# utility_hat.net
KiCad netlist of a schematic drawn in EAGLE
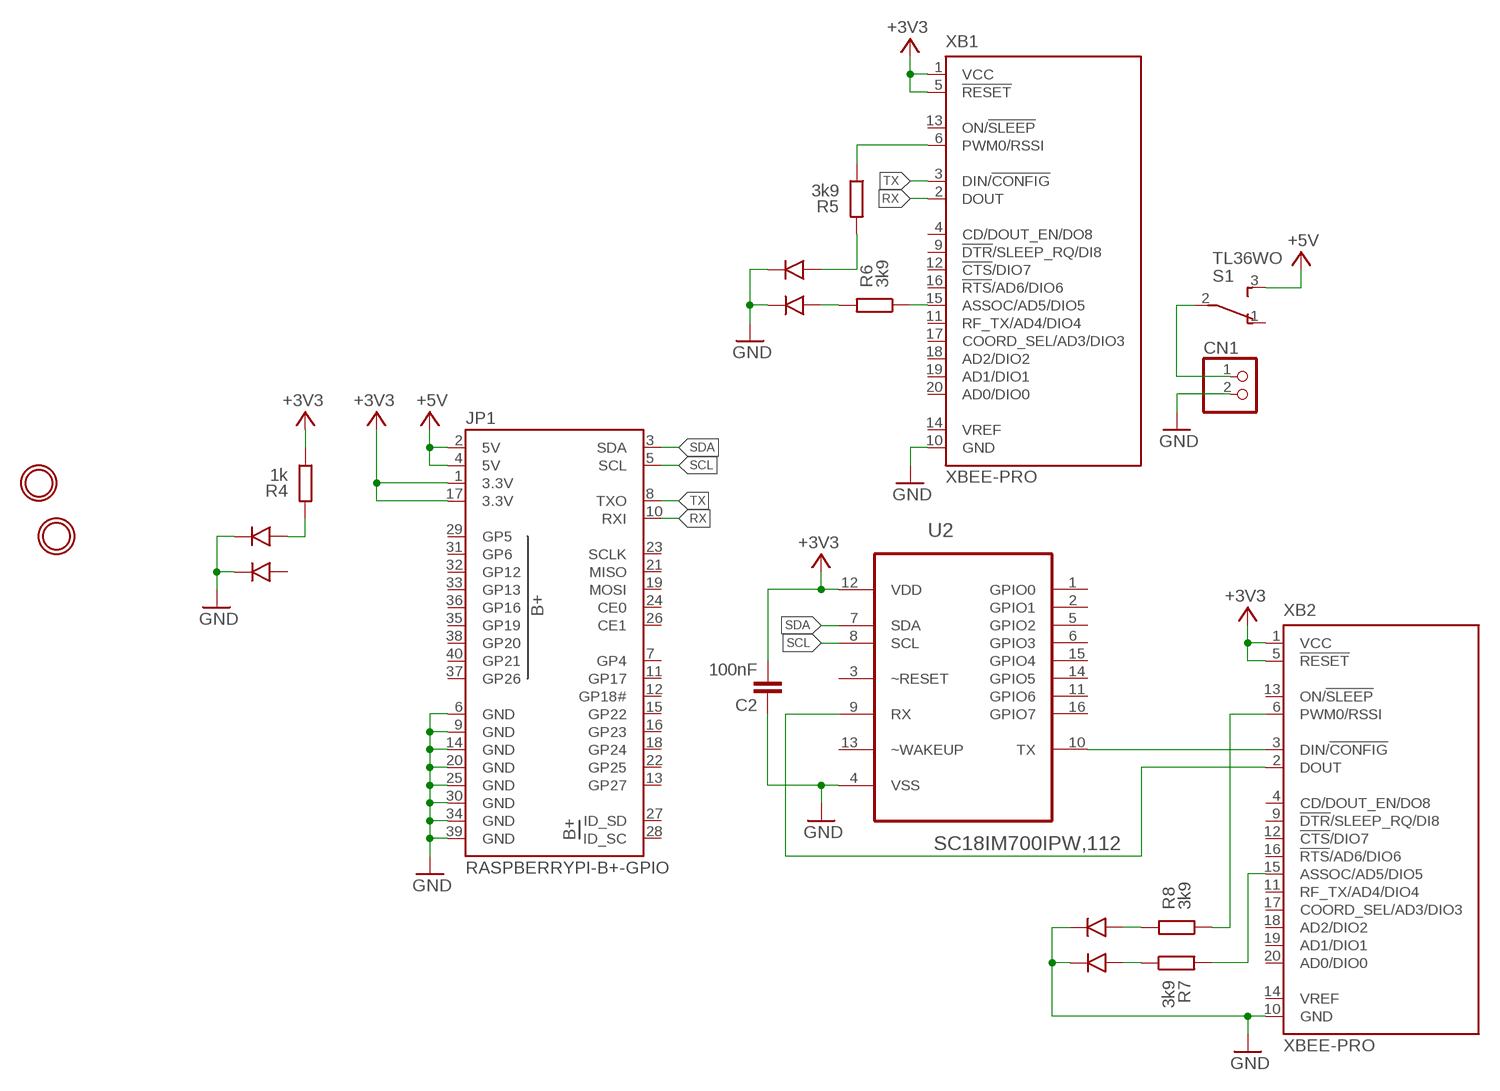
[diagram p0: schematic, sheet 1]

(export (version "E")
  (design (tool "Eeschema 10.0.6"))
  (components
    (comp (ref "C2")
      (value "100nF")
      (footprint "eagle-import:C0805K")
      (libsource (lib "eagle-import") (part "C-EUC0805K"))
    )
    (comp (ref "CN1")
      (value "JST_2PIN")
      (footprint "eagle-import:JSTPH2")
      (libsource (lib "eagle-import") (part "JST_2PIN"))
    )
    (comp (ref "JP1")
      (value "RASPBERRYPI-B+-GPIO")
      (footprint "eagle-import:2X20-SHROUDED")
      (libsource (lib "eagle-import") (part "RASPBERRYPI-B+-GPIO"))
    )
    (comp (ref "R4")
      (value "1k")
      (footprint "eagle-import:M0805")
      (fields (field (name "TOLERANCE") "5%"))
      (libsource (lib "eagle-import") (part "R-EU_M0805"))
    )
    (comp (ref "R5")
      (value "3k9")
      (footprint "eagle-import:M0805")
      (fields (field (name "TOLERANCE") "5%"))
      (libsource (lib "eagle-import") (part "R-EU_M0805"))
    )
    (comp (ref "R6")
      (value "3k9")
      (footprint "eagle-import:M0805")
      (fields (field (name "TOLERANCE") "5%"))
      (libsource (lib "eagle-import") (part "R-EU_M0805"))
    )
    (comp (ref "R7")
      (value "3k9")
      (footprint "eagle-import:M0805")
      (fields (field (name "TOLERANCE") "5%"))
      (libsource (lib "eagle-import") (part "R-EU_M0805"))
    )
    (comp (ref "R8")
      (value "3k9")
      (footprint "eagle-import:M0805")
      (fields (field (name "TOLERANCE") "5%"))
      (libsource (lib "eagle-import") (part "R-EU_M0805"))
    )
    (comp (ref "S1")
      (value "TL36WO")
      (footprint "eagle-import:TL3XWO")
      (libsource (lib "eagle-import") (part "TL36WO"))
    )
    (comp (ref "U$1")
      (value "BI-LEVEL-LED-INDICATOR")
      (footprint "eagle-import:BI-LEVEL-LED-INDICATOR")
      (libsource (lib "eagle-import") (part "BI-LEVEL-LED-INDICATOR"))
    )
    (comp (ref "U$2")
      (value "BI-LEVEL-LED-INDICATOR")
      (footprint "eagle-import:BI-LEVEL-LED-INDICATOR")
      (libsource (lib "eagle-import") (part "BI-LEVEL-LED-INDICATOR"))
    )
    (comp (ref "U$3")
      (value "BI-LEVEL-LED-INDICATOR")
      (footprint "eagle-import:BI-LEVEL-LED-INDICATOR")
      (libsource (lib "eagle-import") (part "BI-LEVEL-LED-INDICATOR"))
    )
    (comp (ref "U$4")
      (value "MOUNTINGHOLE3.0THIN")
      (footprint "eagle-import:MOUNTINGHOLE_3.0_PLATEDTHIN")
      (libsource (lib "eagle-import") (part "MOUNTINGHOLE3.0THIN"))
    )
    (comp (ref "U$5")
      (value "MOUNTINGHOLE3.0THIN")
      (footprint "eagle-import:MOUNTINGHOLE_3.0_PLATEDTHIN")
      (libsource (lib "eagle-import") (part "MOUNTINGHOLE3.0THIN"))
    )
    (comp (ref "U2")
      (value "SC18IM700IPW,112")
      (footprint "eagle-import:SOP65P640X110-16N")
      (libsource (lib "eagle-import") (part "SC18IM700IPW,112"))
    )
    (comp (ref "XB1")
      (value "XBEE-PRO")
      (footprint "eagle-import:XBEE-PRO")
      (fields (field (name "MPN") "XBP24-AWI-001"))
      (libsource (lib "eagle-import") (part "XBEE-PRO"))
    )
    (comp (ref "XB2")
      (value "XBEE-PRO")
      (footprint "eagle-import:XBEE-PRO")
      (fields
        (field (name "MPN") "XBP24-AWI-001")
        (field (name "MPN_1") "XBP24-AWI-001")
        (field (name "OC_FARNELL") "1337916")
        (field (name "OC_NEWARK") "42M2667")
      )
      (libsource (lib "eagle-import") (part "XBEE-PRO"))
    )
  )
  (nets
    (net (code "1") (name "+3V3") (class "Default")
      (node (ref "C2") (pin "2") (pinfunction "2_2") (pintype "passive"))
      (node (ref "JP1") (pin "1") (pinfunction "3.3V_1") (pintype "power_in"))
      (node (ref "JP1") (pin "17") (pinfunction "3.3V_17") (pintype "power_in"))
      (node (ref "R4") (pin "1") (pinfunction "1_1") (pintype "passive"))
      (node (ref "U2") (pin "12") (pinfunction "VDD_12") (pintype "power_in"))
      (node (ref "XB1") (pin "1") (pinfunction "VCC_1") (pintype "power_in"))
      (node (ref "XB1") (pin "5") (pinfunction "~{RESET}_5") (pintype "input"))
      (node (ref "XB2") (pin "1") (pinfunction "VCC_1") (pintype "power_in"))
      (node (ref "XB2") (pin "5") (pinfunction "~{RESET}_5") (pintype "input"))
    )
    (net (code "2") (name "+5V") (class "Default")
      (node (ref "JP1") (pin "2") (pinfunction "5V_2") (pintype "power_in"))
      (node (ref "JP1") (pin "4") (pinfunction "5V_4") (pintype "power_in"))
      (node (ref "S1") (pin "3") (pinfunction "S_3") (pintype "passive"))
    )
    (net (code "3") (name "GND") (class "Default")
      (node (ref "C2") (pin "1") (pinfunction "1_1") (pintype "passive"))
      (node (ref "CN1") (pin "2") (pinfunction "2_2") (pintype "passive"))
      (node (ref "JP1") (pin "14") (pinfunction "GND_14") (pintype "power_in"))
      (node (ref "JP1") (pin "20") (pinfunction "GND_20") (pintype "power_in"))
      (node (ref "JP1") (pin "25") (pinfunction "GND_25") (pintype "power_in"))
      (node (ref "JP1") (pin "30") (pinfunction "GND_30") (pintype "power_in"))
      (node (ref "JP1") (pin "34") (pinfunction "GND_34") (pintype "power_in"))
      (node (ref "JP1") (pin "39") (pinfunction "GND_39") (pintype "power_in"))
      (node (ref "JP1") (pin "6") (pinfunction "GND_6") (pintype "power_in"))
      (node (ref "JP1") (pin "9") (pinfunction "GND_9") (pintype "power_in"))
      (node (ref "U$1") (pin "CATHODE1") (pinfunction "CATHODE1_CATHODE1") (pintype "bidirectional"))
      (node (ref "U$1") (pin "CATHODE2") (pinfunction "CATHODE2_CATHODE2") (pintype "bidirectional"))
      (node (ref "U$2") (pin "CATHODE1") (pinfunction "CATHODE1_CATHODE1") (pintype "bidirectional"))
      (node (ref "U$2") (pin "CATHODE2") (pinfunction "CATHODE2_CATHODE2") (pintype "bidirectional"))
      (node (ref "U$3") (pin "CATHODE1") (pinfunction "CATHODE1_CATHODE1") (pintype "bidirectional"))
      (node (ref "U$3") (pin "CATHODE2") (pinfunction "CATHODE2_CATHODE2") (pintype "bidirectional"))
      (node (ref "U2") (pin "4") (pinfunction "VSS_4") (pintype "passive"))
      (node (ref "XB1") (pin "10") (pinfunction "GND_10") (pintype "power_in"))
      (node (ref "XB2") (pin "10") (pinfunction "GND_10") (pintype "power_in"))
    )
    (net (code "4") (name "Net-(R4-Pad2)") (class "Default")
      (node (ref "R4") (pin "2") (pinfunction "2_2") (pintype "passive"))
      (node (ref "U$3") (pin "ANODE1") (pinfunction "ANODE1_ANODE1") (pintype "bidirectional"))
    )
    (net (code "5") (name "Net-(R5-Pad2)") (class "Default")
      (node (ref "R5") (pin "2") (pinfunction "2_2") (pintype "passive"))
      (node (ref "U$1") (pin "ANODE1") (pinfunction "ANODE1_ANODE1") (pintype "bidirectional"))
    )
    (net (code "6") (name "Net-(R6-Pad2)") (class "Default")
      (node (ref "R6") (pin "2") (pinfunction "2_2") (pintype "passive"))
      (node (ref "U$1") (pin "ANODE2") (pinfunction "ANODE2_ANODE2") (pintype "bidirectional"))
    )
    (net (code "7") (name "Net-(R7-Pad1)") (class "Default")
      (node (ref "R7") (pin "1") (pinfunction "1_1") (pintype "passive"))
      (node (ref "U$2") (pin "ANODE2") (pinfunction "ANODE2_ANODE2") (pintype "bidirectional"))
    )
    (net (code "8") (name "Net-(R8-Pad2)") (class "Default")
      (node (ref "R8") (pin "2") (pinfunction "2_2") (pintype "passive"))
      (node (ref "U$2") (pin "ANODE1") (pinfunction "ANODE1_ANODE1") (pintype "bidirectional"))
    )
    (net (code "9") (name "Net-(S1-P)") (class "Default")
      (node (ref "CN1") (pin "1") (pinfunction "1_1") (pintype "passive"))
      (node (ref "S1") (pin "2") (pinfunction "P_2") (pintype "passive"))
    )
    (net (code "10") (name "Net-(U2-RX)") (class "Default")
      (node (ref "U2") (pin "9") (pinfunction "RX_9") (pintype "input"))
      (node (ref "XB2") (pin "2") (pinfunction "DOUT_2") (pintype "output"))
    )
    (net (code "11") (name "Net-(U2-TX)") (class "Default")
      (node (ref "U2") (pin "10") (pinfunction "TX_10") (pintype "output"))
      (node (ref "XB2") (pin "3") (pinfunction "DIN/~{CONFIG}_3") (pintype "input"))
    )
    (net (code "12") (name "Net-(XB1-ASSOC{slash}AD5{slash}DIO5)") (class "Default")
      (node (ref "R6") (pin "1") (pinfunction "1_1") (pintype "passive"))
      (node (ref "XB1") (pin "15") (pinfunction "ASSOC/AD5/DIO5_15") (pintype "bidirectional"))
    )
    (net (code "13") (name "Net-(XB1-PWM0{slash}RSSI)") (class "Default")
      (node (ref "R5") (pin "1") (pinfunction "1_1") (pintype "passive"))
      (node (ref "XB1") (pin "6") (pinfunction "PWM0/RSSI_6") (pintype "output"))
    )
    (net (code "14") (name "Net-(XB2-ASSOC{slash}AD5{slash}DIO5)") (class "Default")
      (node (ref "R7") (pin "2") (pinfunction "2_2") (pintype "passive"))
      (node (ref "XB2") (pin "15") (pinfunction "ASSOC/AD5/DIO5_15") (pintype "bidirectional"))
    )
    (net (code "15") (name "Net-(XB2-PWM0{slash}RSSI)") (class "Default")
      (node (ref "R8") (pin "1") (pinfunction "1_1") (pintype "passive"))
      (node (ref "XB2") (pin "6") (pinfunction "PWM0/RSSI_6") (pintype "output"))
    )
    (net (code "16") (name "RX") (class "Default")
      (node (ref "JP1") (pin "10") (pinfunction "RXI_10") (pintype "input"))
      (node (ref "XB1") (pin "2") (pinfunction "DOUT_2") (pintype "output"))
    )
    (net (code "17") (name "SCL") (class "Default")
      (node (ref "JP1") (pin "5") (pinfunction "SCL_5") (pintype "bidirectional"))
      (node (ref "U2") (pin "8") (pinfunction "SCL_8") (pintype "input"))
    )
    (net (code "18") (name "SDA") (class "Default")
      (node (ref "JP1") (pin "3") (pinfunction "SDA_3") (pintype "bidirectional"))
      (node (ref "U2") (pin "7") (pinfunction "SDA_7") (pintype "bidirectional"))
    )
    (net (code "19") (name "TX") (class "Default")
      (node (ref "JP1") (pin "8") (pinfunction "TXO_8") (pintype "output"))
      (node (ref "XB1") (pin "3") (pinfunction "DIN/~{CONFIG}_3") (pintype "input"))
    )
    (net (code "20") (name "unconnected-(JP1-CE0-Pad24)") (class "Default")
      (node (ref "JP1") (pin "24") (pinfunction "CE0_24") (pintype "output"))
    )
    (net (code "21") (name "unconnected-(JP1-CE1-Pad26)") (class "Default")
      (node (ref "JP1") (pin "26") (pinfunction "CE1_26") (pintype "output"))
    )
    (net (code "22") (name "unconnected-(JP1-GP4-Pad7)") (class "Default")
      (node (ref "JP1") (pin "7") (pinfunction "GP4_7") (pintype "bidirectional"))
    )
    (net (code "23") (name "unconnected-(JP1-GP5-Pad29)") (class "Default")
      (node (ref "JP1") (pin "29") (pinfunction "GP5_29") (pintype "bidirectional"))
    )
    (net (code "24") (name "unconnected-(JP1-GP6-Pad31)") (class "Default")
      (node (ref "JP1") (pin "31") (pinfunction "GP6_31") (pintype "bidirectional"))
    )
    (net (code "25") (name "unconnected-(JP1-GP12-Pad32)") (class "Default")
      (node (ref "JP1") (pin "32") (pinfunction "GP12_32") (pintype "bidirectional"))
    )
    (net (code "26") (name "unconnected-(JP1-GP13-Pad33)") (class "Default")
      (node (ref "JP1") (pin "33") (pinfunction "GP13_33") (pintype "bidirectional"))
    )
    (net (code "27") (name "unconnected-(JP1-GP16-Pad36)") (class "Default")
      (node (ref "JP1") (pin "36") (pinfunction "GP16_36") (pintype "bidirectional"))
    )
    (net (code "28") (name "unconnected-(JP1-GP17-Pad11)") (class "Default")
      (node (ref "JP1") (pin "11") (pinfunction "GP17_11") (pintype "bidirectional"))
    )
    (net (code "29") (name "unconnected-(JP1-GP18#-Pad12)") (class "Default")
      (node (ref "JP1") (pin "12") (pinfunction "GP18#_12") (pintype "bidirectional"))
    )
    (net (code "30") (name "unconnected-(JP1-GP19-Pad35)") (class "Default")
      (node (ref "JP1") (pin "35") (pinfunction "GP19_35") (pintype "bidirectional"))
    )
    (net (code "31") (name "unconnected-(JP1-GP20-Pad38)") (class "Default")
      (node (ref "JP1") (pin "38") (pinfunction "GP20_38") (pintype "bidirectional"))
    )
    (net (code "32") (name "unconnected-(JP1-GP21-Pad40)") (class "Default")
      (node (ref "JP1") (pin "40") (pinfunction "GP21_40") (pintype "bidirectional"))
    )
    (net (code "33") (name "unconnected-(JP1-GP22-Pad15)") (class "Default")
      (node (ref "JP1") (pin "15") (pinfunction "GP22_15") (pintype "bidirectional"))
    )
    (net (code "34") (name "unconnected-(JP1-GP23-Pad16)") (class "Default")
      (node (ref "JP1") (pin "16") (pinfunction "GP23_16") (pintype "bidirectional"))
    )
    (net (code "35") (name "unconnected-(JP1-GP24-Pad18)") (class "Default")
      (node (ref "JP1") (pin "18") (pinfunction "GP24_18") (pintype "bidirectional"))
    )
    (net (code "36") (name "unconnected-(JP1-GP25-Pad22)") (class "Default")
      (node (ref "JP1") (pin "22") (pinfunction "GP25_22") (pintype "bidirectional"))
    )
    (net (code "37") (name "unconnected-(JP1-GP26-Pad37)") (class "Default")
      (node (ref "JP1") (pin "37") (pinfunction "GP26_37") (pintype "bidirectional"))
    )
    (net (code "38") (name "unconnected-(JP1-GP27-Pad13)") (class "Default")
      (node (ref "JP1") (pin "13") (pinfunction "GP27_13") (pintype "bidirectional"))
    )
    (net (code "39") (name "unconnected-(JP1-ID_SC-Pad28)") (class "Default")
      (node (ref "JP1") (pin "28") (pinfunction "ID_SC_28") (pintype "bidirectional"))
    )
    (net (code "40") (name "unconnected-(JP1-ID_SD-Pad27)") (class "Default")
      (node (ref "JP1") (pin "27") (pinfunction "ID_SD_27") (pintype "bidirectional"))
    )
    (net (code "41") (name "unconnected-(JP1-MISO-Pad21)") (class "Default")
      (node (ref "JP1") (pin "21") (pinfunction "MISO_21") (pintype "input"))
    )
    (net (code "42") (name "unconnected-(JP1-MOSI-Pad19)") (class "Default")
      (node (ref "JP1") (pin "19") (pinfunction "MOSI_19") (pintype "output"))
    )
    (net (code "43") (name "unconnected-(JP1-SCLK-Pad23)") (class "Default")
      (node (ref "JP1") (pin "23") (pinfunction "SCLK_23") (pintype "output"))
    )
    (net (code "44") (name "unconnected-(S1-O-Pad1)") (class "Default")
      (node (ref "S1") (pin "1") (pinfunction "O_1") (pintype "passive"))
    )
    (net (code "45") (name "unconnected-(U$3-PadANODE2)") (class "Default")
      (node (ref "U$3") (pin "ANODE2") (pinfunction "ANODE2_ANODE2") (pintype "bidirectional"))
    )
    (net (code "46") (name "unconnected-(U2-GPIO0-Pad1)") (class "Default")
      (node (ref "U2") (pin "1") (pinfunction "GPIO0_1") (pintype "bidirectional"))
    )
    (net (code "47") (name "unconnected-(U2-GPIO1-Pad2)") (class "Default")
      (node (ref "U2") (pin "2") (pinfunction "GPIO1_2") (pintype "bidirectional"))
    )
    (net (code "48") (name "unconnected-(U2-GPIO2-Pad5)") (class "Default")
      (node (ref "U2") (pin "5") (pinfunction "GPIO2_5") (pintype "bidirectional"))
    )
    (net (code "49") (name "unconnected-(U2-GPIO3-Pad6)") (class "Default")
      (node (ref "U2") (pin "6") (pinfunction "GPIO3_6") (pintype "bidirectional"))
    )
    (net (code "50") (name "unconnected-(U2-GPIO4-Pad15)") (class "Default")
      (node (ref "U2") (pin "15") (pinfunction "GPIO4_15") (pintype "bidirectional"))
    )
    (net (code "51") (name "unconnected-(U2-GPIO5-Pad14)") (class "Default")
      (node (ref "U2") (pin "14") (pinfunction "GPIO5_14") (pintype "bidirectional"))
    )
    (net (code "52") (name "unconnected-(U2-GPIO6-Pad11)") (class "Default")
      (node (ref "U2") (pin "11") (pinfunction "GPIO6_11") (pintype "bidirectional"))
    )
    (net (code "53") (name "unconnected-(U2-GPIO7-Pad16)") (class "Default")
      (node (ref "U2") (pin "16") (pinfunction "GPIO7_16") (pintype "bidirectional"))
    )
    (net (code "54") (name "unconnected-(U2-~{RESET}-Pad3)") (class "Default")
      (node (ref "U2") (pin "3") (pinfunction "~{RESET}_3") (pintype "input"))
    )
    (net (code "55") (name "unconnected-(U2-~{WAKEUP}-Pad13)") (class "Default")
      (node (ref "U2") (pin "13") (pinfunction "~{WAKEUP}_13") (pintype "input"))
    )
    (net (code "56") (name "unconnected-(XB1-AD0{slash}DIO0-Pad20)") (class "Default")
      (node (ref "XB1") (pin "20") (pinfunction "AD0/DIO0_20") (pintype "bidirectional"))
    )
    (net (code "57") (name "unconnected-(XB1-AD1{slash}DIO1-Pad19)") (class "Default")
      (node (ref "XB1") (pin "19") (pinfunction "AD1/DIO1_19") (pintype "bidirectional"))
    )
    (net (code "58") (name "unconnected-(XB1-AD2{slash}DIO2-Pad18)") (class "Default")
      (node (ref "XB1") (pin "18") (pinfunction "AD2/DIO2_18") (pintype "bidirectional"))
    )
    (net (code "59") (name "unconnected-(XB1-CD{slash}DOUT_EN{slash}DO8-Pad4)") (class "Default")
      (node (ref "XB1") (pin "4") (pinfunction "CD/DOUT_EN/DO8_4") (pintype "output"))
    )
    (net (code "60") (name "unconnected-(XB1-COORD_SEL{slash}AD3{slash}DIO3-Pad17)") (class "Default")
      (node (ref "XB1") (pin "17") (pinfunction "COORD_SEL/AD3/DIO3_17") (pintype "bidirectional"))
    )
    (net (code "61") (name "unconnected-(XB1-ON{slash}~{SLEEP}-Pad13)") (class "Default")
      (node (ref "XB1") (pin "13") (pinfunction "ON/~{SLEEP}_13") (pintype "output"))
    )
    (net (code "62") (name "unconnected-(XB1-RF_TX{slash}AD4{slash}DIO4-Pad11)") (class "Default")
      (node (ref "XB1") (pin "11") (pinfunction "RF_TX/AD4/DIO4_11") (pintype "bidirectional"))
    )
    (net (code "63") (name "unconnected-(XB1-VREF-Pad14)") (class "Default")
      (node (ref "XB1") (pin "14") (pinfunction "VREF_14") (pintype "input"))
    )
    (net (code "64") (name "unconnected-(XB1-~{CTS}{slash}DIO7-Pad12)") (class "Default")
      (node (ref "XB1") (pin "12") (pinfunction "~{CTS}/DIO7_12") (pintype "bidirectional"))
    )
    (net (code "65") (name "unconnected-(XB1-~{DTR}{slash}SLEEP_RQ{slash}DI8-Pad9)") (class "Default")
      (node (ref "XB1") (pin "9") (pinfunction "~{DTR}/SLEEP_RQ/DI8_9") (pintype "bidirectional"))
    )
    (net (code "66") (name "unconnected-(XB1-~{RTS}{slash}AD6{slash}DIO6-Pad16)") (class "Default")
      (node (ref "XB1") (pin "16") (pinfunction "~{RTS}/AD6/DIO6_16") (pintype "bidirectional"))
    )
    (net (code "67") (name "unconnected-(XB2-AD0{slash}DIO0-Pad20)") (class "Default")
      (node (ref "XB2") (pin "20") (pinfunction "AD0/DIO0_20") (pintype "bidirectional"))
    )
    (net (code "68") (name "unconnected-(XB2-AD1{slash}DIO1-Pad19)") (class "Default")
      (node (ref "XB2") (pin "19") (pinfunction "AD1/DIO1_19") (pintype "bidirectional"))
    )
    (net (code "69") (name "unconnected-(XB2-AD2{slash}DIO2-Pad18)") (class "Default")
      (node (ref "XB2") (pin "18") (pinfunction "AD2/DIO2_18") (pintype "bidirectional"))
    )
    (net (code "70") (name "unconnected-(XB2-CD{slash}DOUT_EN{slash}DO8-Pad4)") (class "Default")
      (node (ref "XB2") (pin "4") (pinfunction "CD/DOUT_EN/DO8_4") (pintype "output"))
    )
    (net (code "71") (name "unconnected-(XB2-COORD_SEL{slash}AD3{slash}DIO3-Pad17)") (class "Default")
      (node (ref "XB2") (pin "17") (pinfunction "COORD_SEL/AD3/DIO3_17") (pintype "bidirectional"))
    )
    (net (code "72") (name "unconnected-(XB2-ON{slash}~{SLEEP}-Pad13)") (class "Default")
      (node (ref "XB2") (pin "13") (pinfunction "ON/~{SLEEP}_13") (pintype "output"))
    )
    (net (code "73") (name "unconnected-(XB2-RF_TX{slash}AD4{slash}DIO4-Pad11)") (class "Default")
      (node (ref "XB2") (pin "11") (pinfunction "RF_TX/AD4/DIO4_11") (pintype "bidirectional"))
    )
    (net (code "74") (name "unconnected-(XB2-VREF-Pad14)") (class "Default")
      (node (ref "XB2") (pin "14") (pinfunction "VREF_14") (pintype "input"))
    )
    (net (code "75") (name "unconnected-(XB2-~{CTS}{slash}DIO7-Pad12)") (class "Default")
      (node (ref "XB2") (pin "12") (pinfunction "~{CTS}/DIO7_12") (pintype "bidirectional"))
    )
    (net (code "76") (name "unconnected-(XB2-~{DTR}{slash}SLEEP_RQ{slash}DI8-Pad9)") (class "Default")
      (node (ref "XB2") (pin "9") (pinfunction "~{DTR}/SLEEP_RQ/DI8_9") (pintype "bidirectional"))
    )
    (net (code "77") (name "unconnected-(XB2-~{RTS}{slash}AD6{slash}DIO6-Pad16)") (class "Default")
      (node (ref "XB2") (pin "16") (pinfunction "~{RTS}/AD6/DIO6_16") (pintype "bidirectional"))
    )
  )
)
